# COM-MSP430FR5994.net
KiCad netlist of a schematic drawn in Altium Designer
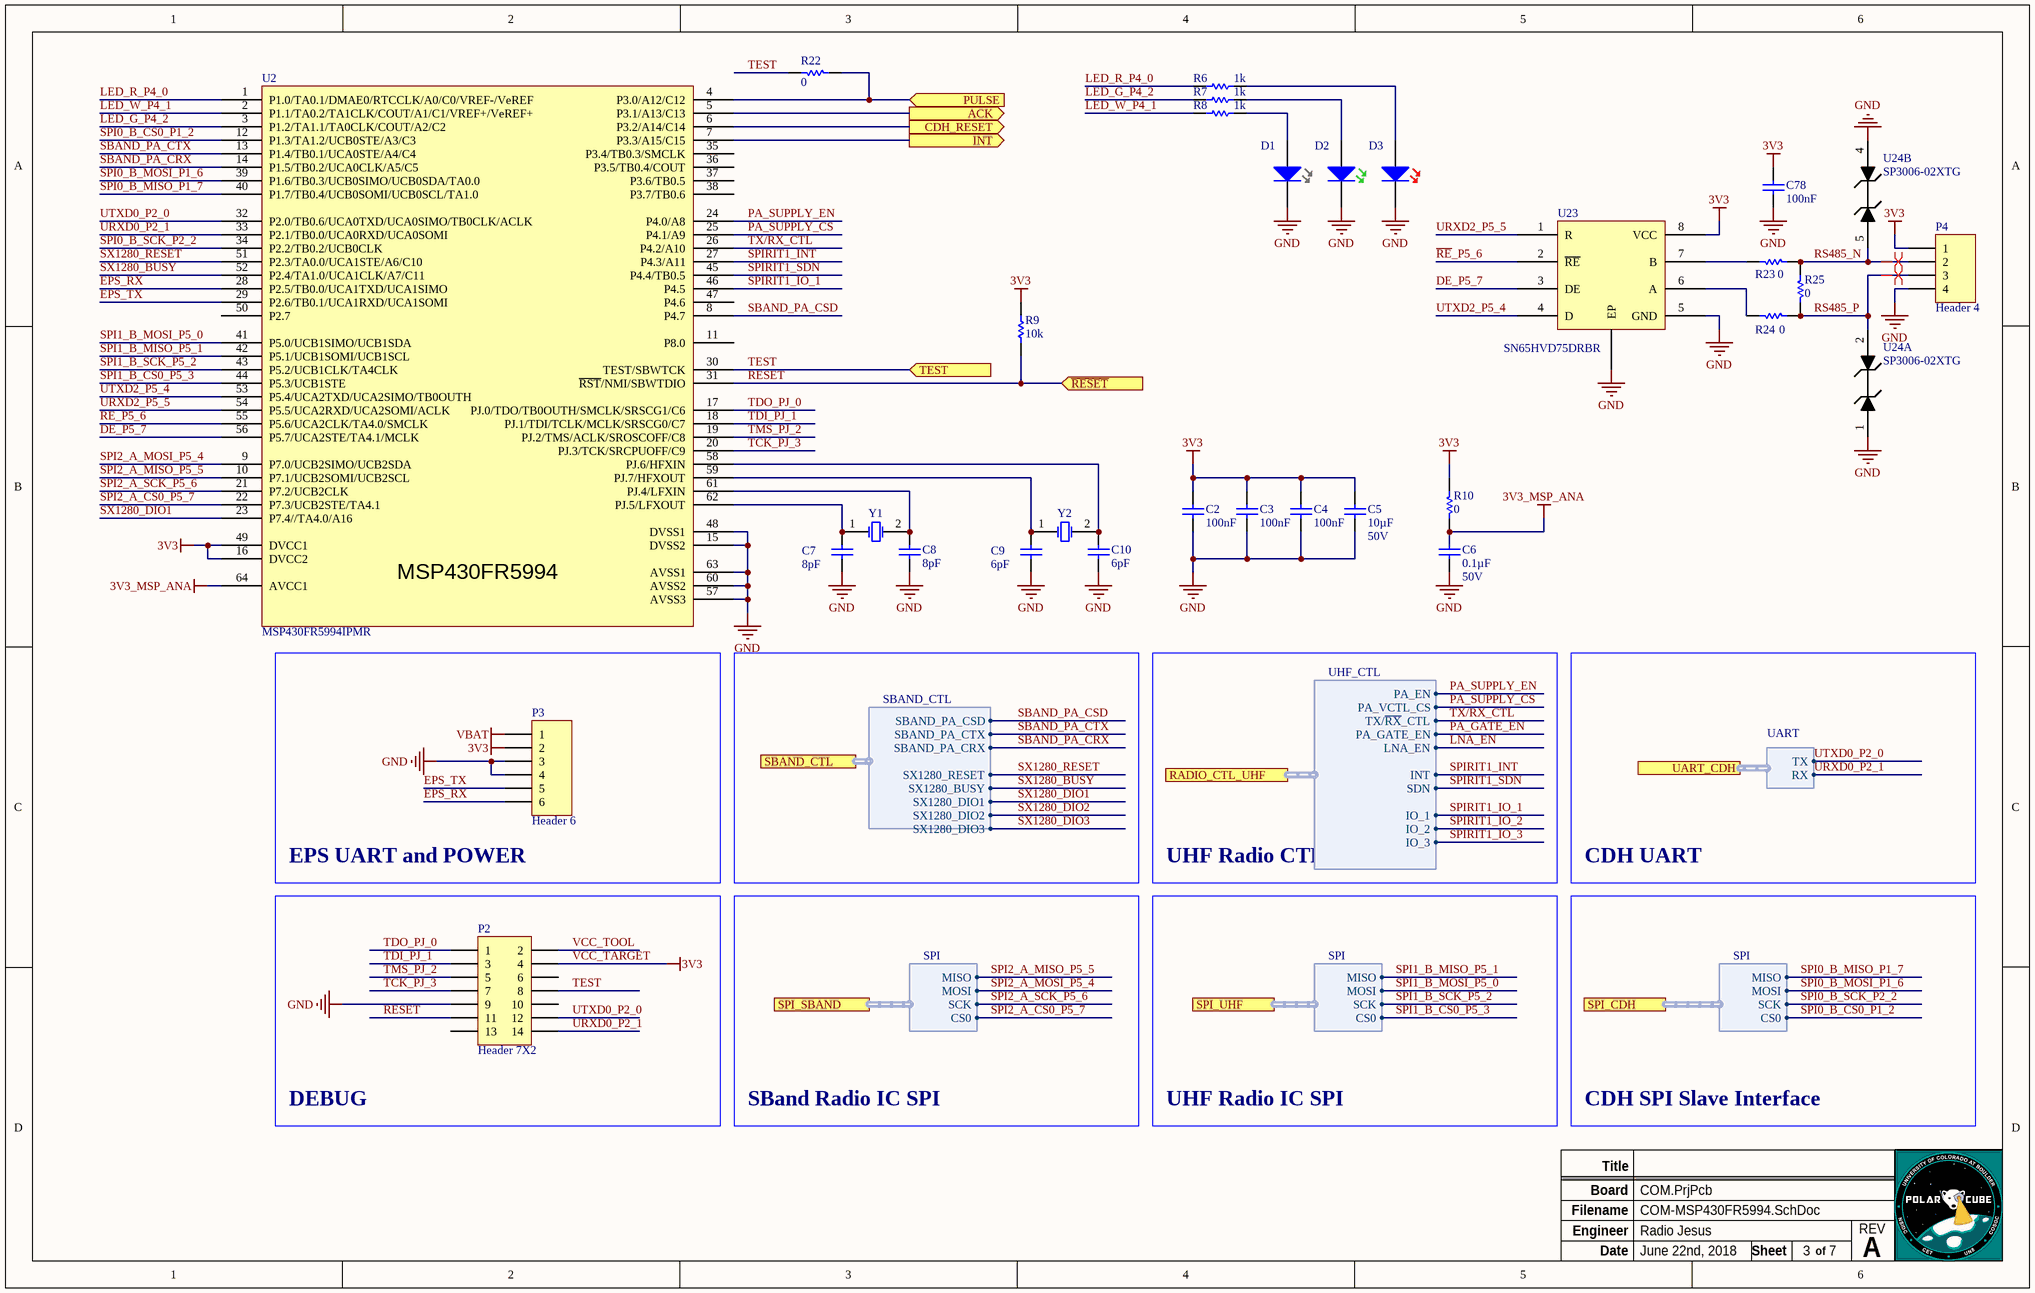
[diagram p0: COM-MSP430FR5994.SchDoc]

(export (version "E")
  (design (tool "Eeschema 10.0.6"))
  (components
    (comp (ref "C2")
      (value "CL10B104KB8ZW6C")
      (footprint "1608[0603]")
      (description "MLCC 1608(0603) X7R 100NF 10% 50")
      (fields
        (field (name "CAPACITANCE") "100nF")
        (field (name "PARTNUMBER") "CGA3E2X7R1H104K080AA")
        (field (name "MANUFACTURER") "TDK")
      )
      (libsource (lib "PolarCube") (part "Cap"))
    )
    (comp (ref "C3")
      (value "CL10B104KB8ZW6C")
      (footprint "1608[0603]")
      (description "MLCC 1608(0603) X7R 100NF 10% 50")
      (fields
        (field (name "CAPACITANCE") "100nF")
        (field (name "PARTNUMBER") "CGA3E2X7R1H104K080AA")
        (field (name "MANUFACTURER") "TDK")
      )
      (libsource (lib "PolarCube") (part "Cap"))
    )
    (comp (ref "C4")
      (value "CL10B104KB8ZW6C")
      (footprint "1608[0603]")
      (description "MLCC 1608(0603) X7R 100NF 10% 50")
      (fields
        (field (name "CAPACITANCE") "100nF")
        (field (name "PARTNUMBER") "CGA3E2X7R1H104K080AA")
        (field (name "MANUFACTURER") "TDK")
      )
      (libsource (lib "PolarCube") (part "Cap"))
    )
    (comp (ref "C5")
      (value "CL10A106KP8NNNC")
      (footprint "1608[0603]")
      (description "CAP CER 10UF 10V X5R 0603")
      (fields
        (field (name "CAPACITANCE") "10µF")
        (field (name "VOLTAGE") "50V")
        (field (name "PARTNUMBER") "CGA3E2X7R1H104K080AA")
        (field (name "MANUFACTURER") "TDK")
      )
      (libsource (lib "PolarCube") (part "Cap"))
    )
    (comp (ref "C6")
      (value "CL10B104KB8ZW6C")
      (footprint "1608[0603]")
      (description "MLCC 1608(0603) X7R 100NF 10% 50")
      (fields
        (field (name "CAPACITANCE") "0.1µF")
        (field (name "VOLTAGE") "50V")
        (field (name "PARTNUMBER") "CGA3E2X7R1H104K080AA")
        (field (name "MANUFACTURER") "TDK")
      )
      (libsource (lib "PolarCube") (part "Cap"))
    )
    (comp (ref "C7")
      (value "CL10C080CB8NNNC")
      (footprint "1608[0603]")
      (description "CAP CER 8PF 50V C0G/NP0 0603")
      (fields
        (field (name "CAPACITANCE") "8pF")
        (field (name "PARTNUMBER") "CGA3E2X7R1H104K080AA")
        (field (name "MANUFACTURER") "TDK")
      )
      (libsource (lib "PolarCube") (part "Cap"))
    )
    (comp (ref "C8")
      (value "CL10C080CB8NNNC")
      (footprint "1608[0603]")
      (description "CAP CER 8PF 50V C0G/NP0 0603")
      (fields
        (field (name "CAPACITANCE") "8pF")
        (field (name "PARTNUMBER") "CGA3E2X7R1H104K080AA")
        (field (name "MANUFACTURER") "TDK")
      )
      (libsource (lib "PolarCube") (part "Cap"))
    )
    (comp (ref "C9")
      (value "CL10C060CB8NCNC")
      (footprint "1608[0603]")
      (description "CAP CER 6PF 50V C0G/NP0 0603")
      (fields
        (field (name "CAPACITANCE") "6pF")
        (field (name "PARTNUMBER") "CGA3E2X7R1H104K080AA")
        (field (name "MANUFACTURER") "TDK")
      )
      (libsource (lib "PolarCube") (part "Cap"))
    )
    (comp (ref "C10")
      (value "CL10C060CB8NCNC")
      (footprint "1608[0603]")
      (description "CAP CER 6PF 50V C0G/NP0 0603")
      (fields
        (field (name "CAPACITANCE") "6pF")
        (field (name "PARTNUMBER") "CGA3E2X7R1H104K080AA")
        (field (name "MANUFACTURER") "TDK")
      )
      (libsource (lib "PolarCube") (part "Cap"))
    )
    (comp (ref "C78")
      (value "CL10B104KB8ZW6C")
      (footprint "CAPC0603X03L")
      (description "MLCC 1608(0603) X7R 100NF 10% 50")
      (fields
        (field (name "CAPACITANCE") "100nF")
        (field (name "PARTNUMBER") "CGA3E2X7R1H104K080AA")
        (field (name "MANUFACTURER") "TDK")
      )
      (libsource (lib "PolarCube") (part "Cap"))
    )
    (comp (ref "D1")
      (value "QBLP601-IW")
      (footprint "1608[0603]")
      (description "White LED Indication - Discrete 3.2V 0603 (1608 Metric)")
      (fields (field (name "PARTNUMBER") "SMLP13WBC8W") (field (name "MANUFACTURER") "Rohm Semiconductor"))
      (libsource (lib "PolarCube") (part "LED_WHITE"))
    )
    (comp (ref "D2")
      (value "150060VS75000")
      (footprint "1608[0603]")
      (description "Green 570nm LED Indication - Discrete 2V 0603 (1608 Metric)")
      (fields (field (name "PARTNUMBER") "SML-P11MTT86") (field (name "MANUFACTURER") "Rohm Semiconductor"))
      (libsource (lib "PolarCube") (part "LED_GREEN"))
    )
    (comp (ref "D3")
      (value "150060RS75000")
      (footprint "1608[0603]")
      (description "Red 625nm LED Indication - Discrete 2V 0603 (1608 Metric)")
      (fields (field (name "PARTNUMBER") "SML-P11UTT86") (field (name "MANUFACTURER") "Rohm Semiconductor"))
      (libsource (lib "PolarCube") (part "LED_RED"))
    )
    (comp (ref "P2")
      (value "Header 7X2")
      (footprint "MSP430_JTAG_HEADER")
      (description "Header, 7-Pin, Dual row")
      (fields (field (name "PUBLISHER") "Altium Limited"))
      (libsource (lib "Miscellaneous Connectors") (part "Header 7X2"))
    )
    (comp (ref "P3")
      (value "Header 6")
      (footprint "T1M-06-F-SV-L")
      (description "Header, 6-Pin")
      (fields (field (name "PUBLISHER") "Altium Limited"))
      (libsource (lib "Miscellaneous Connectors") (part "Header 6"))
    )
    (comp (ref "P4")
      (value "Header 4")
      (footprint "FH34SRJ-4S-0.5SH(99)")
      (description "Header, 4-Pin")
      (fields (field (name "PUBLISHER") "Altium Limited"))
      (libsource (lib "Miscellaneous Connectors") (part "Header 4"))
    )
    (comp (ref "R6")
      (value "RMCF0603JT1K00")
      (footprint "1608[0603]")
      (description "RES 1K OHM 5% 1/10W 0603")
      (fields
        (field (name "RESISTANCE") "1k")
        (field (name "PARTNUMBER") "ERJ-2GEJ102X")
        (field (name "MANUFACTURER") "Panasonic")
      )
      (libsource (lib "PolarCube") (part "Res"))
    )
    (comp (ref "R7")
      (value "RMCF0603JT1K00")
      (footprint "1608[0603]")
      (description "RES 1K OHM 5% 1/10W 0603")
      (fields
        (field (name "RESISTANCE") "1k")
        (field (name "PARTNUMBER") "ERJ-2GEJ102X")
        (field (name "MANUFACTURER") "Panasonic")
      )
      (libsource (lib "PolarCube") (part "Res"))
    )
    (comp (ref "R8")
      (value "RMCF0603JT1K00")
      (footprint "1608[0603]")
      (description "RES 1K OHM 5% 1/10W 0603")
      (fields
        (field (name "RESISTANCE") "1k")
        (field (name "PARTNUMBER") "ERJ-2GEJ102X")
        (field (name "MANUFACTURER") "Panasonic")
      )
      (libsource (lib "PolarCube") (part "Res"))
    )
    (comp (ref "R9")
      (value "RMCF0603JG10K0")
      (footprint "1608[0603]")
      (description "10 kOhms ±5% 0.1W, 1/10W Chip Resistor 0603 (1608 Metric) Automotive AEC-Q200 Thick Film")
      (fields
        (field (name "RESISTANCE") "10k")
        (field (name "PARTNUMBER") "CRCW060310K0FKEA")
        (field (name "MANUFACTURER") "Vishay")
      )
      (libsource (lib "PolarCube") (part "Res"))
    )
    (comp (ref "R10")
      (value "CRCW06030000Z0EAC")
      (footprint "1608[0603]")
      (description "RES SMD 0 OHM JUMP 1/10W 0603")
      (fields
        (field (name "RESISTANCE") "0")
        (field (name "PARTNUMBER") "CRCW060310K0FKEA")
        (field (name "MANUFACTURER") "Vishay")
      )
      (libsource (lib "PolarCube") (part "Res"))
    )
    (comp (ref "R22")
      (value "CRCW06030000Z0EAC")
      (footprint "1608[0603]")
      (description "RES SMD 0 OHM JUMP 1/10W 0603")
      (fields
        (field (name "RESISTANCE") "0")
        (field (name "PARTNUMBER") "CRCW060310K0FKEA")
        (field (name "MANUFACTURER") "Vishay")
      )
      (libsource (lib "PolarCube") (part "Res"))
    )
    (comp (ref "R23")
      (value "CRCW06030000Z0EAC")
      (footprint "RESC0603X03N")
      (description "RES SMD 0 OHM JUMP 1/10W 0603")
      (fields
        (field (name "RESISTANCE") "0")
        (field (name "PARTNUMBER") "CRCW060310K0FKEA")
        (field (name "MANUFACTURER") "Vishay")
      )
      (libsource (lib "PolarCube") (part "Res"))
    )
    (comp (ref "R24")
      (value "CRCW06030000Z0EAC")
      (footprint "RESC0603X03N")
      (description "RES SMD 0 OHM JUMP 1/10W 0603")
      (fields
        (field (name "RESISTANCE") "0")
        (field (name "PARTNUMBER") "CRCW060310K0FKEA")
        (field (name "MANUFACTURER") "Vishay")
      )
      (libsource (lib "PolarCube") (part "Res"))
    )
    (comp (ref "R25")
      (value "CRCW06030000Z0EAC")
      (footprint "RESC0603X03N")
      (description "RES SMD 0 OHM JUMP 1/10W 0603")
      (fields
        (field (name "RESISTANCE") "0")
        (field (name "PARTNUMBER") "CRCW060310K0FKEA")
        (field (name "MANUFACTURER") "Vishay")
      )
      (libsource (lib "PolarCube") (part "Res"))
    )
    (comp (ref "U2")
      (value "MSP430FR5994IPMR")
      (footprint "S-PQFP-G64")
      (description "CPUXV2 MSP430™ FRAM Microcontroller IC 16-Bit 16MHz 256KB (256K x 8) FRAM 64-LQFP (10x10)")
      (libsource (lib "Cesium_3") (part "MSP430FR5994IPMR"))
    )
    (comp (ref "U23")
      (value "SN65HVD75DRBR")
      (footprint "SON65P300X100_HS-9N")
      (libsource (lib "Cesium_3") (part "SN65HVD75DRBR"))
    )
    (comp (ref "U24")
      (value "SP3006-02XTG")
      (footprint "SOT50P160X60-6L")
      (description "TVS DIODE 6V 15V SOT563")
      (libsource (lib "Cesium_3") (part "SP3006-02XTG"))
    )
    (comp (ref "Y1")
      (value "XTAL")
      (footprint "FC-135R")
      (description "Crystal Oscillator")
      (fields (field (name "PUBLISHER") "Altium Limited"))
      (libsource (lib "Miscellaneous Devices") (part "XTAL"))
    )
    (comp (ref "Y2")
      (value "XTAL")
      (footprint "NX3225GD")
      (description "Crystal Oscillator")
      (fields (field (name "PUBLISHER") "Altium Limited"))
      (libsource (lib "Miscellaneous Devices") (part "XTAL"))
    )
  )
  (nets
    (net (code "5") (name "/ACK") (class "Default")
      (node (ref "U2") (pin "5") (pinfunction "P3.1/A13/C13_5") (pintype "passive"))
    )
    (net (code "6") (name "/CDH_RESET") (class "Default")
      (node (ref "U2") (pin "6") (pinfunction "P3.2/A14/C14_6") (pintype "passive"))
    )
    (net (code "7") (name "/DE_P5_7") (class "Default")
      (node (ref "U2") (pin "56") (pinfunction "P5.7/UCA2STE/TA4.1/MCLK_56") (pintype "passive"))
      (node (ref "U23") (pin "3") (pinfunction "DE_3") (pintype "passive"))
    )
    (net (code "8") (name "/EPS_RX") (class "Default")
      (node (ref "P3") (pin "6") (pinfunction "6_6") (pintype "passive"))
      (node (ref "U2") (pin "28") (pinfunction "P2.5/TB0.0/UCA1TXD/UCA1SIMO_28") (pintype "passive"))
    )
    (net (code "9") (name "/EPS_TX") (class "Default")
      (node (ref "P3") (pin "5") (pinfunction "5_5") (pintype "passive"))
      (node (ref "U2") (pin "29") (pinfunction "P2.6/TB0.1/UCA1RXD/UCA1SOMI_29") (pintype "passive"))
    )
    (net (code "10") (name "/INT") (class "Default")
      (node (ref "U2") (pin "7") (pinfunction "P3.3/A15/C15_7") (pintype "passive"))
    )
    (net (code "11") (name "/LED_G_P4_2") (class "Default")
      (node (ref "R7") (pin "1") (pinfunction "1_1") (pintype "passive"))
      (node (ref "U2") (pin "3") (pinfunction "P1.2/TA1.1/TA0CLK/COUT/A2/C2_3") (pintype "passive"))
    )
    (net (code "12") (name "/LED_R_P4_0") (class "Default")
      (node (ref "R6") (pin "1") (pinfunction "1_1") (pintype "passive"))
      (node (ref "U2") (pin "1") (pinfunction "P1.0/TA0.1/DMAE0/RTCCLK/A0/C0/VREF-/VeREF_1") (pintype "passive"))
    )
    (net (code "13") (name "/LED_W_P4_1") (class "Default")
      (node (ref "R8") (pin "1") (pinfunction "1_1") (pintype "passive"))
      (node (ref "U2") (pin "2") (pinfunction "P1.1/TA0.2/TA1CLK/COUT/A1/C1/VREF+/VeREF+_2") (pintype "passive"))
    )
    (net (code "16") (name "/PA_SUPPLY_CS") (class "Default")
      (node (ref "U2") (pin "25") (pinfunction "P4.1/A9_25") (pintype "passive"))
    )
    (net (code "17") (name "/PA_SUPPLY_EN") (class "Default")
      (node (ref "U2") (pin "24") (pinfunction "P4.0/A8_24") (pintype "passive"))
    )
    (net (code "18") (name "/PULSE") (class "Default")
      (node (ref "R22") (pin "2") (pinfunction "2_2") (pintype "passive"))
      (node (ref "U2") (pin "4") (pinfunction "P3.0/A12/C12_4") (pintype "passive"))
    )
    (net (code "19") (name "/RS485_N") (class "Default")
      (node (ref "P4") (pin "2") (pinfunction "2_2") (pintype "passive"))
      (node (ref "R23") (pin "2") (pinfunction "2_2") (pintype "passive"))
      (node (ref "R25") (pin "2") (pinfunction "2_2") (pintype "passive"))
      (node (ref "U24") (pin "5") (pintype "passive"))
    )
    (net (code "20") (name "/RS485_P") (class "Default")
      (node (ref "P4") (pin "3") (pinfunction "3_3") (pintype "passive"))
      (node (ref "R24") (pin "2") (pinfunction "2_2") (pintype "passive"))
      (node (ref "R25") (pin "1") (pinfunction "1_1") (pintype "passive"))
      (node (ref "U24") (pin "2") (pintype "passive"))
    )
    (net (code "21") (name "/SBAND_PA_CRX") (class "Default")
      (node (ref "U2") (pin "14") (pinfunction "P1.5/TB0.2/UCA0CLK/A5/C5_14") (pintype "passive"))
    )
    (net (code "22") (name "/SBAND_PA_CSD") (class "Default")
      (node (ref "U2") (pin "8") (pinfunction "P4.7_8") (pintype "passive"))
    )
    (net (code "23") (name "/SBAND_PA_CTX") (class "Default")
      (node (ref "U2") (pin "13") (pinfunction "P1.4/TB0.1/UCA0STE/A4/C4_13") (pintype "passive"))
    )
    (net (code "24") (name "/SPI0_B_CS0_P1_2") (class "Default")
      (node (ref "U2") (pin "12") (pinfunction "P1.3/TA1.2/UCB0STE/A3/C3_12") (pintype "passive"))
    )
    (net (code "25") (name "/SPI0_B_MISO_P1_7") (class "Default")
      (node (ref "U2") (pin "40") (pinfunction "P1.7/TB0.4/UCB0SOMI/UCB0SCL/TA1.0_40") (pintype "passive"))
    )
    (net (code "26") (name "/SPI0_B_MOSI_P1_6") (class "Default")
      (node (ref "U2") (pin "39") (pinfunction "P1.6/TB0.3/UCB0SIMO/UCB0SDA/TA0.0_39") (pintype "passive"))
    )
    (net (code "27") (name "/SPI0_B_SCK_P2_2") (class "Default")
      (node (ref "U2") (pin "34") (pinfunction "P2.2/TB0.2/UCB0CLK_34") (pintype "passive"))
    )
    (net (code "28") (name "/SPI1_B_CS0_P5_3") (class "Default")
      (node (ref "U2") (pin "44") (pinfunction "P5.3/UCB1STE_44") (pintype "passive"))
    )
    (net (code "29") (name "/SPI1_B_MISO_P5_1") (class "Default")
      (node (ref "U2") (pin "42") (pinfunction "P5.1/UCB1SOMI/UCB1SCL_42") (pintype "passive"))
    )
    (net (code "30") (name "/SPI1_B_MOSI_P5_0") (class "Default")
      (node (ref "U2") (pin "41") (pinfunction "P5.0/UCB1SIMO/UCB1SDA_41") (pintype "passive"))
    )
    (net (code "31") (name "/SPI1_B_SCK_P5_2") (class "Default")
      (node (ref "U2") (pin "43") (pinfunction "P5.2/UCB1CLK/TA4CLK_43") (pintype "passive"))
    )
    (net (code "32") (name "/SPI2_A_CS0_P5_7") (class "Default")
      (node (ref "U2") (pin "22") (pinfunction "P7.3/UCB2STE/TA4.1_22") (pintype "passive"))
    )
    (net (code "33") (name "/SPI2_A_MISO_P5_5") (class "Default")
      (node (ref "U2") (pin "10") (pinfunction "P7.1/UCB2SOMI/UCB2SCL_10") (pintype "passive"))
    )
    (net (code "34") (name "/SPI2_A_MOSI_P5_4") (class "Default")
      (node (ref "U2") (pin "9") (pinfunction "P7.0/UCB2SIMO/UCB2SDA_9") (pintype "passive"))
    )
    (net (code "35") (name "/SPI2_A_SCK_P5_6") (class "Default")
      (node (ref "U2") (pin "21") (pinfunction "P7.2/UCB2CLK_21") (pintype "passive"))
    )
    (net (code "36") (name "/SPIRIT1_INT") (class "Default")
      (node (ref "U2") (pin "27") (pinfunction "P4.3/A11_27") (pintype "passive"))
    )
    (net (code "37") (name "/SPIRIT1_IO_1") (class "Default")
      (node (ref "U2") (pin "46") (pinfunction "P4.5_46") (pintype "passive"))
    )
    (net (code "40") (name "/SPIRIT1_SDN") (class "Default")
      (node (ref "U2") (pin "45") (pinfunction "P4.4/TB0.5_45") (pintype "passive"))
    )
    (net (code "41") (name "/SX1280_BUSY") (class "Default")
      (node (ref "U2") (pin "52") (pinfunction "P2.4/TA1.0/UCA1CLK/A7/C11_52") (pintype "passive"))
    )
    (net (code "42") (name "/SX1280_DIO1") (class "Default")
      (node (ref "U2") (pin "23") (pinfunction "P7.4//TA4.0/A16_23") (pintype "passive"))
    )
    (net (code "45") (name "/SX1280_RESET") (class "Default")
      (node (ref "U2") (pin "51") (pinfunction "P2.3/TA0.0/UCA1STE/A6/C10_51") (pintype "passive"))
    )
    (net (code "46") (name "/TCK_PJ_3") (class "Default")
      (node (ref "P2") (pin "7") (pinfunction "7_7") (pintype "passive"))
      (node (ref "U2") (pin "20") (pinfunction "PJ.3/TCK/SRCPUOFF/C9_20") (pintype "passive"))
    )
    (net (code "47") (name "/TDI_PJ_1") (class "Default")
      (node (ref "P2") (pin "3") (pinfunction "3_3") (pintype "passive"))
      (node (ref "U2") (pin "18") (pinfunction "PJ.1/TDI/TCLK/MCLK/SRSCG0/C7_18") (pintype "passive"))
    )
    (net (code "48") (name "/TDO_PJ_0") (class "Default")
      (node (ref "P2") (pin "1") (pinfunction "1_1") (pintype "passive"))
      (node (ref "U2") (pin "17") (pinfunction "PJ.0/TDO/TB0OUTH/SMCLK/SRSCG1/C6_17") (pintype "passive"))
    )
    (net (code "49") (name "/TEST") (class "Default")
      (node (ref "P2") (pin "8") (pinfunction "8_8") (pintype "passive"))
      (node (ref "R22") (pin "1") (pinfunction "1_1") (pintype "passive"))
      (node (ref "U2") (pin "30") (pinfunction "TEST/SBWTCK_30") (pintype "passive"))
    )
    (net (code "50") (name "/TMS_PJ_2") (class "Default")
      (node (ref "P2") (pin "5") (pinfunction "5_5") (pintype "passive"))
      (node (ref "U2") (pin "19") (pinfunction "PJ.2/TMS/ACLK/SROSCOFF/C8_19") (pintype "passive"))
    )
    (net (code "51") (name "/TX{slash}~{RX}_CTL") (class "Default")
      (node (ref "U2") (pin "26") (pinfunction "P4.2/A10_26") (pintype "passive"))
    )
    (net (code "52") (name "/URXD0_P2_1") (class "Default")
      (node (ref "P2") (pin "14") (pinfunction "14_14") (pintype "passive"))
      (node (ref "U2") (pin "33") (pinfunction "P2.1/TB0.0/UCA0RXD/UCA0SOMI_33") (pintype "passive"))
    )
    (net (code "53") (name "/URXD2_P5_5") (class "Default")
      (node (ref "U2") (pin "54") (pinfunction "P5.5/UCA2RXD/UCA2SOMI/ACLK_54") (pintype "passive"))
      (node (ref "U23") (pin "1") (pinfunction "R_1") (pintype "passive"))
    )
    (net (code "54") (name "/UTXD0_P2_0") (class "Default")
      (node (ref "P2") (pin "12") (pinfunction "12_12") (pintype "passive"))
      (node (ref "U2") (pin "32") (pinfunction "P2.0/TB0.6/UCA0TXD/UCA0SIMO/TB0CLK/ACLK_32") (pintype "passive"))
    )
    (net (code "55") (name "/UTXD2_P5_4") (class "Default")
      (node (ref "U2") (pin "53") (pinfunction "P5.4/UCA2TXD/UCA2SIMO/TB0OUTH_53") (pintype "passive"))
      (node (ref "U23") (pin "4") (pinfunction "D_4") (pintype "passive"))
    )
    (net (code "56") (name "/VCC_TOOL") (class "Default")
      (node (ref "P2") (pin "2") (pinfunction "2_2") (pintype "passive"))
    )
    (net (code "61") (name "/~{RESET}") (class "Default")
      (node (ref "P2") (pin "11") (pinfunction "11_11") (pintype "passive"))
      (node (ref "R9") (pin "1") (pinfunction "1_1") (pintype "passive"))
      (node (ref "U2") (pin "31") (pinfunction "~{RST}/NMI/SBWTDIO_31") (pintype "passive"))
    )
    (net (code "62") (name "/~{RE}_P5_6") (class "Default")
      (node (ref "U2") (pin "55") (pinfunction "P5.6/UCA2CLK/TA4.0/SMCLK_55") (pintype "passive"))
      (node (ref "U23") (pin "2") (pinfunction "~{RE}_2") (pintype "passive"))
    )
    (net (code "63") (name "3V3") (class "Default")
      (node (ref "C2") (pin "2") (pinfunction "2_2") (pintype "passive"))
      (node (ref "C3") (pin "2") (pinfunction "2_2") (pintype "passive"))
      (node (ref "C4") (pin "2") (pinfunction "2_2") (pintype "passive"))
      (node (ref "C5") (pin "2") (pinfunction "2_2") (pintype "passive"))
      (node (ref "C78") (pin "2") (pinfunction "2_2") (pintype "passive"))
      (node (ref "P2") (pin "4") (pinfunction "4_4") (pintype "passive"))
      (node (ref "P3") (pin "2") (pinfunction "2_2") (pintype "passive"))
      (node (ref "P4") (pin "1") (pinfunction "1_1") (pintype "passive"))
      (node (ref "R10") (pin "1") (pinfunction "1_1") (pintype "passive"))
      (node (ref "R9") (pin "2") (pinfunction "2_2") (pintype "passive"))
      (node (ref "U2") (pin "16") (pinfunction "DVCC2_16") (pintype "passive"))
      (node (ref "U2") (pin "49") (pinfunction "DVCC1_49") (pintype "passive"))
      (node (ref "U23") (pin "8") (pinfunction "VCC_8") (pintype "passive"))
    )
    (net (code "64") (name "3V3_MSP_ANA") (class "Default")
      (node (ref "C6") (pin "2") (pinfunction "2_2") (pintype "passive"))
      (node (ref "R10") (pin "2") (pinfunction "2_2") (pintype "passive"))
      (node (ref "U2") (pin "64") (pinfunction "AVCC1_64") (pintype "passive"))
    )
    (net (code "65") (name "GND") (class "Default")
      (node (ref "C10") (pin "1") (pinfunction "1_1") (pintype "passive"))
      (node (ref "C2") (pin "1") (pinfunction "1_1") (pintype "passive"))
      (node (ref "C3") (pin "1") (pinfunction "1_1") (pintype "passive"))
      (node (ref "C4") (pin "1") (pinfunction "1_1") (pintype "passive"))
      (node (ref "C5") (pin "1") (pinfunction "1_1") (pintype "passive"))
      (node (ref "C6") (pin "1") (pinfunction "1_1") (pintype "passive"))
      (node (ref "C7") (pin "1") (pinfunction "1_1") (pintype "passive"))
      (node (ref "C78") (pin "1") (pinfunction "1_1") (pintype "passive"))
      (node (ref "C8") (pin "1") (pinfunction "1_1") (pintype "passive"))
      (node (ref "C9") (pin "1") (pinfunction "1_1") (pintype "passive"))
      (node (ref "D1") (pin "2") (pinfunction "K_2") (pintype "passive"))
      (node (ref "D2") (pin "2") (pinfunction "K_2") (pintype "passive"))
      (node (ref "D3") (pin "2") (pinfunction "K_2") (pintype "passive"))
      (node (ref "P2") (pin "9") (pinfunction "9_9") (pintype "passive"))
      (node (ref "P3") (pin "3") (pinfunction "3_3") (pintype "passive"))
      (node (ref "P3") (pin "4") (pinfunction "4_4") (pintype "passive"))
      (node (ref "P4") (pin "4") (pinfunction "4_4") (pintype "passive"))
      (node (ref "U2") (pin "15") (pinfunction "DVSS2_15") (pintype "passive"))
      (node (ref "U2") (pin "48") (pinfunction "DVSS1_48") (pintype "passive"))
      (node (ref "U2") (pin "57") (pinfunction "AVSS3_57") (pintype "passive"))
      (node (ref "U2") (pin "60") (pinfunction "AVSS2_60") (pintype "passive"))
      (node (ref "U2") (pin "63") (pinfunction "AVSS1_63") (pintype "passive"))
      (node (ref "U23") (pin "5") (pinfunction "GND_5") (pintype "passive"))
      (node (ref "U23") (pin "9") (pinfunction "EP_9") (pintype "passive"))
      (node (ref "U24") (pin "1") (pintype "passive"))
      (node (ref "U24") (pin "4") (pintype "passive"))
    )
    (net (code "66") (name "Net-(D1-A)") (class "Default")
      (node (ref "D1") (pin "1") (pinfunction "A_1") (pintype "passive"))
      (node (ref "R8") (pin "2") (pinfunction "2_2") (pintype "passive"))
    )
    (net (code "67") (name "Net-(D2-A)") (class "Default")
      (node (ref "D2") (pin "1") (pinfunction "A_1") (pintype "passive"))
      (node (ref "R7") (pin "2") (pinfunction "2_2") (pintype "passive"))
    )
    (net (code "68") (name "Net-(D3-A)") (class "Default")
      (node (ref "D3") (pin "1") (pinfunction "A_1") (pintype "passive"))
      (node (ref "R6") (pin "2") (pinfunction "2_2") (pintype "passive"))
    )
    (net (code "69") (name "Net-(U2-PJ.4{slash}LFXIN)") (class "Default")
      (node (ref "C8") (pin "2") (pinfunction "2_2") (pintype "passive"))
      (node (ref "U2") (pin "61") (pinfunction "PJ.4/LFXIN_61") (pintype "passive"))
      (node (ref "Y1") (pin "2") (pinfunction "OSC2_2") (pintype "passive"))
    )
    (net (code "70") (name "Net-(U2-PJ.5{slash}LFXOUT)") (class "Default")
      (node (ref "C7") (pin "2") (pinfunction "2_2") (pintype "passive"))
      (node (ref "U2") (pin "62") (pinfunction "PJ.5/LFXOUT_62") (pintype "passive"))
      (node (ref "Y1") (pin "1") (pinfunction "OSC1_1") (pintype "passive"))
    )
    (net (code "71") (name "Net-(U2-PJ.6{slash}HFXIN)") (class "Default")
      (node (ref "C10") (pin "2") (pinfunction "2_2") (pintype "passive"))
      (node (ref "U2") (pin "58") (pinfunction "PJ.6/HFXIN_58") (pintype "passive"))
      (node (ref "Y2") (pin "2") (pinfunction "OSC2_2") (pintype "passive"))
    )
    (net (code "72") (name "Net-(U2-PJ.7{slash}HFXOUT)") (class "Default")
      (node (ref "C9") (pin "2") (pinfunction "2_2") (pintype "passive"))
      (node (ref "U2") (pin "59") (pinfunction "PJ.7/HFXOUT_59") (pintype "passive"))
      (node (ref "Y2") (pin "1") (pinfunction "OSC1_1") (pintype "passive"))
    )
    (net (code "73") (name "Net-(U23-A)") (class "Default")
      (node (ref "R24") (pin "1") (pinfunction "1_1") (pintype "passive"))
      (node (ref "U23") (pin "6") (pinfunction "A_6") (pintype "passive"))
    )
    (net (code "74") (name "Net-(U23-B)") (class "Default")
      (node (ref "R23") (pin "1") (pinfunction "1_1") (pintype "passive"))
      (node (ref "U23") (pin "7") (pinfunction "B_7") (pintype "passive"))
    )
    (net (code "75") (name "VBAT") (class "Default")
      (node (ref "P3") (pin "1") (pinfunction "1_1") (pintype "passive"))
    )
    (net (code "76") (name "unconnected-(P2-Pad6)") (class "Default")
      (node (ref "P2") (pin "6") (pinfunction "6_6") (pintype "passive"))
    )
    (net (code "77") (name "unconnected-(P2-Pad10)") (class "Default")
      (node (ref "P2") (pin "10") (pinfunction "10_10") (pintype "passive"))
    )
    (net (code "78") (name "unconnected-(P2-Pad13)") (class "Default")
      (node (ref "P2") (pin "13") (pinfunction "13_13") (pintype "passive"))
    )
    (net (code "79") (name "unconnected-(U2-P2.7-Pad50)") (class "Default")
      (node (ref "U2") (pin "50") (pinfunction "P2.7_50") (pintype "passive"))
    )
    (net (code "80") (name "unconnected-(U2-P3.4{slash}TB0.3{slash}SMCLK-Pad35)") (class "Default")
      (node (ref "U2") (pin "35") (pinfunction "P3.4/TB0.3/SMCLK_35") (pintype "passive"))
    )
    (net (code "81") (name "unconnected-(U2-P3.5{slash}TB0.4{slash}COUT-Pad36)") (class "Default")
      (node (ref "U2") (pin "36") (pinfunction "P3.5/TB0.4/COUT_36") (pintype "passive"))
    )
    (net (code "82") (name "unconnected-(U2-P3.6{slash}TB0.5-Pad37)") (class "Default")
      (node (ref "U2") (pin "37") (pinfunction "P3.6/TB0.5_37") (pintype "passive"))
    )
    (net (code "83") (name "unconnected-(U2-P3.7{slash}TB0.6-Pad38)") (class "Default")
      (node (ref "U2") (pin "38") (pinfunction "P3.7/TB0.6_38") (pintype "passive"))
    )
    (net (code "84") (name "unconnected-(U2-P4.6-Pad47)") (class "Default")
      (node (ref "U2") (pin "47") (pinfunction "P4.6_47") (pintype "passive"))
    )
    (net (code "85") (name "unconnected-(U2-P8.0-Pad11)") (class "Default")
      (node (ref "U2") (pin "11") (pinfunction "P8.0_11") (pintype "passive"))
    )
  )
)
